# Auunuciator.net
KiCad netlist of a schematic drawn in Altium Designer
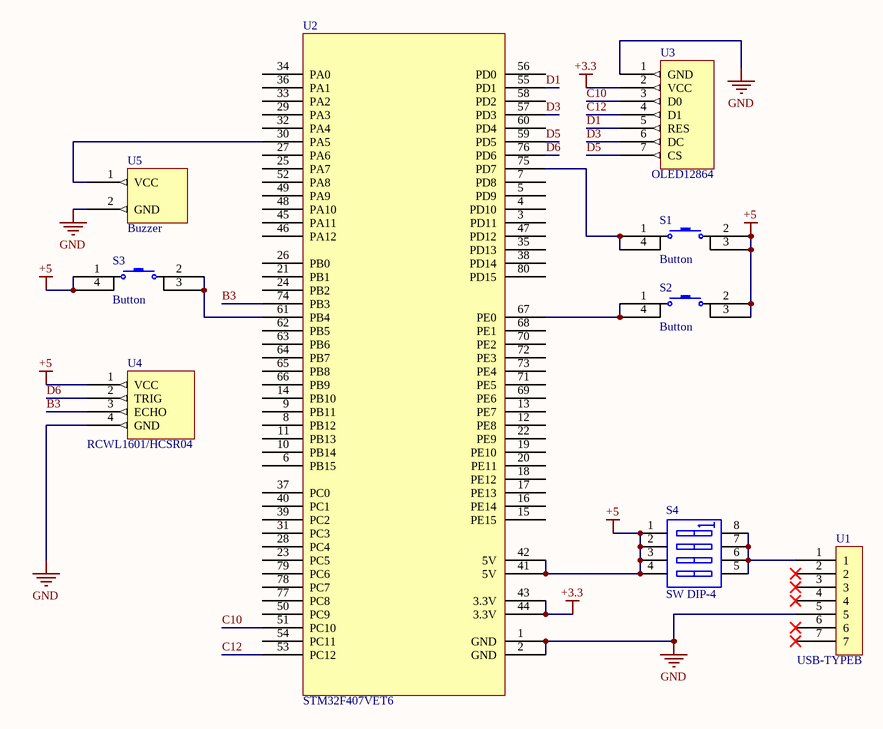
[diagram p0: Auunuciator.SchDoc]

(export (version "E")
  (design (tool "Eeschema 10.0.6"))
  (components
    (comp (ref "S1") (value "Button") (libsource (lib "User SchLib") (part "4PinButton")))
    (comp (ref "S2") (value "Button") (libsource (lib "User SchLib") (part "4PinButton")))
    (comp (ref "S3") (value "Button") (libsource (lib "User SchLib") (part "4PinButton")))
    (comp (ref "S4")
      (value "SW DIP-4")
      (footprint "DIP-8")
      (description "DIP Switch, 4 Position, SPST")
      (fields (field (name "PUBLISHER") "Altium Limited"))
      (libsource (lib "Miscellaneous Devices") (part "SW DIP-4"))
    )
    (comp (ref "U1")
      (value "USB-TYPEB")
      (footprint "microB USB Breakout")
      (libsource (lib "private") (part "HEAD7A"))
    )
    (comp (ref "U2")
      (value "STM32F407VET6")
      (footprint "FK407M1")
      (libsource (lib "核心板元件库") (part "FK407M1"))
    )
    (comp (ref "U3")
      (value "OLED12864")
      (footprint "HDR1X7")
      (description "OLED")
      (libsource (lib "User SchLib") (part "OLED12864"))
    )
    (comp (ref "U4")
      (value "RCWL1601/HCSR04")
      (footprint "HDR1X4")
      (description "Ranging Module")
      (libsource (lib "User SchLib") (part "RCWL1601/HCSR04"))
    )
    (comp (ref "U5")
      (value "Buzzer")
      (footprint "THDZ")
      (description "Active")
      (libsource (lib "User SchLib") (part "Buzzer"))
    )
  )
  (nets
    (net (code "1") (name "+3.3") (class "Default")
      (node (ref "U2") (pin "43") (pinfunction "3.3V_43") (pintype "passive"))
      (node (ref "U2") (pin "44") (pinfunction "3.3V_44") (pintype "passive"))
      (node (ref "U3") (pin "2") (pinfunction "VCC_2") (pintype "output"))
    )
    (net (code "2") (name "+5") (class "Default")
      (node (ref "S1") (pin "2") (pintype "open_collector"))
      (node (ref "S1") (pin "3") (pintype "open_collector"))
      (node (ref "S2") (pin "2") (pintype "open_collector"))
      (node (ref "S2") (pin "3") (pintype "open_collector"))
      (node (ref "S3") (pin "1") (pintype "open_collector"))
      (node (ref "S3") (pin "4") (pintype "open_collector"))
      (node (ref "S4") (pin "1") (pinfunction "A1_1") (pintype "passive"))
      (node (ref "S4") (pin "2") (pinfunction "A2_2") (pintype "passive"))
      (node (ref "S4") (pin "3") (pinfunction "A3_3") (pintype "passive"))
      (node (ref "S4") (pin "4") (pinfunction "A4_4") (pintype "passive"))
      (node (ref "U2") (pin "41") (pinfunction "5V_41") (pintype "passive"))
      (node (ref "U2") (pin "42") (pinfunction "5V_42") (pintype "passive"))
      (node (ref "U4") (pin "1") (pinfunction "VCC_1") (pintype "output"))
    )
    (net (code "3") (name "/B3") (class "Default")
      (node (ref "U2") (pin "74") (pinfunction "PB3_74") (pintype "passive"))
      (node (ref "U4") (pin "3") (pinfunction "ECHO_3") (pintype "output"))
    )
    (net (code "4") (name "/C10") (class "Default")
      (node (ref "U2") (pin "51") (pinfunction "PC10_51") (pintype "passive"))
      (node (ref "U3") (pin "3") (pinfunction "D0_3") (pintype "output"))
    )
    (net (code "5") (name "/C12") (class "Default")
      (node (ref "U2") (pin "53") (pinfunction "PC12_53") (pintype "passive"))
      (node (ref "U3") (pin "4") (pinfunction "D1_4") (pintype "output"))
    )
    (net (code "6") (name "/D1") (class "Default")
      (node (ref "U2") (pin "55") (pinfunction "PD1_55") (pintype "passive"))
      (node (ref "U3") (pin "5") (pinfunction "RES_5") (pintype "output"))
    )
    (net (code "7") (name "/D3") (class "Default")
      (node (ref "U2") (pin "57") (pinfunction "PD3_57") (pintype "passive"))
      (node (ref "U3") (pin "6") (pinfunction "DC_6") (pintype "output"))
    )
    (net (code "8") (name "/D5") (class "Default")
      (node (ref "U2") (pin "59") (pinfunction "PD5_59") (pintype "passive"))
      (node (ref "U3") (pin "7") (pinfunction "CS_7") (pintype "output"))
    )
    (net (code "9") (name "/D6") (class "Default")
      (node (ref "U2") (pin "76") (pinfunction "PD6_76") (pintype "passive"))
      (node (ref "U4") (pin "2") (pinfunction "TRIG_2") (pintype "output"))
    )
    (net (code "10") (name "GND") (class "Default")
      (node (ref "U1") (pin "5") (pinfunction "5_5") (pintype "passive"))
      (node (ref "U2") (pin "1") (pinfunction "GND_1") (pintype "passive"))
      (node (ref "U2") (pin "2") (pinfunction "GND_2") (pintype "passive"))
      (node (ref "U3") (pin "1") (pinfunction "GND_1") (pintype "output"))
      (node (ref "U4") (pin "4") (pinfunction "GND_4") (pintype "output"))
      (node (ref "U5") (pin "2") (pinfunction "GND_2") (pintype "output"))
    )
    (net (code "11") (name "Net-(S4-B1)") (class "Default")
      (node (ref "S4") (pin "5") (pinfunction "B4_5") (pintype "passive"))
      (node (ref "S4") (pin "6") (pinfunction "B3_6") (pintype "passive"))
      (node (ref "S4") (pin "7") (pinfunction "B2_7") (pintype "passive"))
      (node (ref "S4") (pin "8") (pinfunction "B1_8") (pintype "passive"))
      (node (ref "U1") (pin "1") (pinfunction "1_1") (pintype "passive"))
    )
    (net (code "12") (name "Net-(U2-PA5)") (class "Default")
      (node (ref "U2") (pin "30") (pinfunction "PA5_30") (pintype "passive"))
      (node (ref "U5") (pin "1") (pinfunction "VCC_1") (pintype "output"))
    )
    (net (code "13") (name "Net-(U2-PB4)") (class "Default")
      (node (ref "S3") (pin "2") (pintype "open_collector"))
      (node (ref "S3") (pin "3") (pintype "open_collector"))
      (node (ref "U2") (pin "61") (pinfunction "PB4_61") (pintype "passive"))
    )
    (net (code "14") (name "Net-(U2-PD7)") (class "Default")
      (node (ref "S1") (pin "1") (pintype "open_collector"))
      (node (ref "S1") (pin "4") (pintype "open_collector"))
      (node (ref "U2") (pin "75") (pinfunction "PD7_75") (pintype "passive"))
    )
    (net (code "15") (name "Net-(U2-PE0)") (class "Default")
      (node (ref "S2") (pin "1") (pintype "open_collector"))
      (node (ref "S2") (pin "4") (pintype "open_collector"))
      (node (ref "U2") (pin "67") (pinfunction "PE0_67") (pintype "passive"))
    )
    (net (code "16") (name "unconnected-(U1-Pad2)") (class "Default")
      (node (ref "U1") (pin "2") (pinfunction "2_2") (pintype "passive+no_connect"))
    )
    (net (code "17") (name "unconnected-(U1-Pad3)") (class "Default")
      (node (ref "U1") (pin "3") (pinfunction "3_3") (pintype "passive+no_connect"))
    )
    (net (code "18") (name "unconnected-(U1-Pad4)") (class "Default")
      (node (ref "U1") (pin "4") (pinfunction "4_4") (pintype "passive+no_connect"))
    )
    (net (code "19") (name "unconnected-(U1-Pad6)") (class "Default")
      (node (ref "U1") (pin "6") (pinfunction "6_6") (pintype "passive+no_connect"))
    )
    (net (code "20") (name "unconnected-(U1-Pad7)") (class "Default")
      (node (ref "U1") (pin "7") (pinfunction "7_7") (pintype "passive+no_connect"))
    )
    (net (code "21") (name "unconnected-(U2-PA0-Pad34)") (class "Default")
      (node (ref "U2") (pin "34") (pinfunction "PA0_34") (pintype "passive"))
    )
    (net (code "22") (name "unconnected-(U2-PA1-Pad36)") (class "Default")
      (node (ref "U2") (pin "36") (pinfunction "PA1_36") (pintype "passive"))
    )
    (net (code "23") (name "unconnected-(U2-PA2-Pad33)") (class "Default")
      (node (ref "U2") (pin "33") (pinfunction "PA2_33") (pintype "passive"))
    )
    (net (code "24") (name "unconnected-(U2-PA3-Pad29)") (class "Default")
      (node (ref "U2") (pin "29") (pinfunction "PA3_29") (pintype "passive"))
    )
    (net (code "25") (name "unconnected-(U2-PA4-Pad32)") (class "Default")
      (node (ref "U2") (pin "32") (pinfunction "PA4_32") (pintype "passive"))
    )
    (net (code "26") (name "unconnected-(U2-PA6-Pad27)") (class "Default")
      (node (ref "U2") (pin "27") (pinfunction "PA6_27") (pintype "passive"))
    )
    (net (code "27") (name "unconnected-(U2-PA7-Pad25)") (class "Default")
      (node (ref "U2") (pin "25") (pinfunction "PA7_25") (pintype "passive"))
    )
    (net (code "28") (name "unconnected-(U2-PA8-Pad52)") (class "Default")
      (node (ref "U2") (pin "52") (pinfunction "PA8_52") (pintype "passive"))
    )
    (net (code "29") (name "unconnected-(U2-PA9-Pad49)") (class "Default")
      (node (ref "U2") (pin "49") (pinfunction "PA9_49") (pintype "passive"))
    )
    (net (code "30") (name "unconnected-(U2-PA10-Pad48)") (class "Default")
      (node (ref "U2") (pin "48") (pinfunction "PA10_48") (pintype "passive"))
    )
    (net (code "31") (name "unconnected-(U2-PA11-Pad45)") (class "Default")
      (node (ref "U2") (pin "45") (pinfunction "PA11_45") (pintype "passive"))
    )
    (net (code "32") (name "unconnected-(U2-PA12-Pad46)") (class "Default")
      (node (ref "U2") (pin "46") (pinfunction "PA12_46") (pintype "passive"))
    )
    (net (code "33") (name "unconnected-(U2-PB0-Pad26)") (class "Default")
      (node (ref "U2") (pin "26") (pinfunction "PB0_26") (pintype "passive"))
    )
    (net (code "34") (name "unconnected-(U2-PB1-Pad21)") (class "Default")
      (node (ref "U2") (pin "21") (pinfunction "PB1_21") (pintype "passive"))
    )
    (net (code "35") (name "unconnected-(U2-PB2-Pad24)") (class "Default")
      (node (ref "U2") (pin "24") (pinfunction "PB2_24") (pintype "passive"))
    )
    (net (code "36") (name "unconnected-(U2-PB5-Pad62)") (class "Default")
      (node (ref "U2") (pin "62") (pinfunction "PB5_62") (pintype "passive"))
    )
    (net (code "37") (name "unconnected-(U2-PB6-Pad63)") (class "Default")
      (node (ref "U2") (pin "63") (pinfunction "PB6_63") (pintype "passive"))
    )
    (net (code "38") (name "unconnected-(U2-PB7-Pad64)") (class "Default")
      (node (ref "U2") (pin "64") (pinfunction "PB7_64") (pintype "passive"))
    )
    (net (code "39") (name "unconnected-(U2-PB8-Pad65)") (class "Default")
      (node (ref "U2") (pin "65") (pinfunction "PB8_65") (pintype "passive"))
    )
    (net (code "40") (name "unconnected-(U2-PB9-Pad66)") (class "Default")
      (node (ref "U2") (pin "66") (pinfunction "PB9_66") (pintype "passive"))
    )
    (net (code "41") (name "unconnected-(U2-PB10-Pad14)") (class "Default")
      (node (ref "U2") (pin "14") (pinfunction "PB10_14") (pintype "passive"))
    )
    (net (code "42") (name "unconnected-(U2-PB11-Pad9)") (class "Default")
      (node (ref "U2") (pin "9") (pinfunction "PB11_9") (pintype "passive"))
    )
    (net (code "43") (name "unconnected-(U2-PB12-Pad8)") (class "Default")
      (node (ref "U2") (pin "8") (pinfunction "PB12_8") (pintype "passive"))
    )
    (net (code "44") (name "unconnected-(U2-PB13-Pad11)") (class "Default")
      (node (ref "U2") (pin "11") (pinfunction "PB13_11") (pintype "passive"))
    )
    (net (code "45") (name "unconnected-(U2-PB14-Pad10)") (class "Default")
      (node (ref "U2") (pin "10") (pinfunction "PB14_10") (pintype "passive"))
    )
    (net (code "46") (name "unconnected-(U2-PB15-Pad6)") (class "Default")
      (node (ref "U2") (pin "6") (pinfunction "PB15_6") (pintype "passive"))
    )
    (net (code "47") (name "unconnected-(U2-PC0-Pad37)") (class "Default")
      (node (ref "U2") (pin "37") (pinfunction "PC0_37") (pintype "passive"))
    )
    (net (code "48") (name "unconnected-(U2-PC1-Pad40)") (class "Default")
      (node (ref "U2") (pin "40") (pinfunction "PC1_40") (pintype "passive"))
    )
    (net (code "49") (name "unconnected-(U2-PC2-Pad39)") (class "Default")
      (node (ref "U2") (pin "39") (pinfunction "PC2_39") (pintype "passive"))
    )
    (net (code "50") (name "unconnected-(U2-PC3-Pad31)") (class "Default")
      (node (ref "U2") (pin "31") (pinfunction "PC3_31") (pintype "passive"))
    )
    (net (code "51") (name "unconnected-(U2-PC4-Pad28)") (class "Default")
      (node (ref "U2") (pin "28") (pinfunction "PC4_28") (pintype "passive"))
    )
    (net (code "52") (name "unconnected-(U2-PC5-Pad23)") (class "Default")
      (node (ref "U2") (pin "23") (pinfunction "PC5_23") (pintype "passive"))
    )
    (net (code "53") (name "unconnected-(U2-PC6-Pad79)") (class "Default")
      (node (ref "U2") (pin "79") (pinfunction "PC6_79") (pintype "passive"))
    )
    (net (code "54") (name "unconnected-(U2-PC7-Pad78)") (class "Default")
      (node (ref "U2") (pin "78") (pinfunction "PC7_78") (pintype "passive"))
    )
    (net (code "55") (name "unconnected-(U2-PC8-Pad77)") (class "Default")
      (node (ref "U2") (pin "77") (pinfunction "PC8_77") (pintype "passive"))
    )
    (net (code "56") (name "unconnected-(U2-PC9-Pad50)") (class "Default")
      (node (ref "U2") (pin "50") (pinfunction "PC9_50") (pintype "passive"))
    )
    (net (code "57") (name "unconnected-(U2-PC11-Pad54)") (class "Default")
      (node (ref "U2") (pin "54") (pinfunction "PC11_54") (pintype "passive"))
    )
    (net (code "58") (name "unconnected-(U2-PD0-Pad56)") (class "Default")
      (node (ref "U2") (pin "56") (pinfunction "PD0_56") (pintype "passive"))
    )
    (net (code "59") (name "unconnected-(U2-PD2-Pad58)") (class "Default")
      (node (ref "U2") (pin "58") (pinfunction "PD2_58") (pintype "passive"))
    )
    (net (code "60") (name "unconnected-(U2-PD4-Pad60)") (class "Default")
      (node (ref "U2") (pin "60") (pinfunction "PD4_60") (pintype "passive"))
    )
    (net (code "61") (name "unconnected-(U2-PD8-Pad7)") (class "Default")
      (node (ref "U2") (pin "7") (pinfunction "PD8_7") (pintype "passive"))
    )
    (net (code "62") (name "unconnected-(U2-PD9-Pad5)") (class "Default")
      (node (ref "U2") (pin "5") (pinfunction "PD9_5") (pintype "passive"))
    )
    (net (code "63") (name "unconnected-(U2-PD10-Pad4)") (class "Default")
      (node (ref "U2") (pin "4") (pinfunction "PD10_4") (pintype "passive"))
    )
    (net (code "64") (name "unconnected-(U2-PD11-Pad3)") (class "Default")
      (node (ref "U2") (pin "3") (pinfunction "PD11_3") (pintype "passive"))
    )
    (net (code "65") (name "unconnected-(U2-PD12-Pad47)") (class "Default")
      (node (ref "U2") (pin "47") (pinfunction "PD12_47") (pintype "passive"))
    )
    (net (code "66") (name "unconnected-(U2-PD13-Pad35)") (class "Default")
      (node (ref "U2") (pin "35") (pinfunction "PD13_35") (pintype "passive"))
    )
    (net (code "67") (name "unconnected-(U2-PD14-Pad38)") (class "Default")
      (node (ref "U2") (pin "38") (pinfunction "PD14_38") (pintype "passive"))
    )
    (net (code "68") (name "unconnected-(U2-PD15-Pad80)") (class "Default")
      (node (ref "U2") (pin "80") (pinfunction "PD15_80") (pintype "passive"))
    )
    (net (code "69") (name "unconnected-(U2-PE1-Pad68)") (class "Default")
      (node (ref "U2") (pin "68") (pinfunction "PE1_68") (pintype "passive"))
    )
    (net (code "70") (name "unconnected-(U2-PE2-Pad70)") (class "Default")
      (node (ref "U2") (pin "70") (pinfunction "PE2_70") (pintype "passive"))
    )
    (net (code "71") (name "unconnected-(U2-PE3-Pad72)") (class "Default")
      (node (ref "U2") (pin "72") (pinfunction "PE3_72") (pintype "passive"))
    )
    (net (code "72") (name "unconnected-(U2-PE4-Pad73)") (class "Default")
      (node (ref "U2") (pin "73") (pinfunction "PE4_73") (pintype "passive"))
    )
    (net (code "73") (name "unconnected-(U2-PE5-Pad71)") (class "Default")
      (node (ref "U2") (pin "71") (pinfunction "PE5_71") (pintype "passive"))
    )
    (net (code "74") (name "unconnected-(U2-PE6-Pad69)") (class "Default")
      (node (ref "U2") (pin "69") (pinfunction "PE6_69") (pintype "passive"))
    )
    (net (code "75") (name "unconnected-(U2-PE7-Pad13)") (class "Default")
      (node (ref "U2") (pin "13") (pinfunction "PE7_13") (pintype "passive"))
    )
    (net (code "76") (name "unconnected-(U2-PE8-Pad12)") (class "Default")
      (node (ref "U2") (pin "12") (pinfunction "PE8_12") (pintype "passive"))
    )
    (net (code "77") (name "unconnected-(U2-PE9-Pad22)") (class "Default")
      (node (ref "U2") (pin "22") (pinfunction "PE9_22") (pintype "passive"))
    )
    (net (code "78") (name "unconnected-(U2-PE10-Pad19)") (class "Default")
      (node (ref "U2") (pin "19") (pinfunction "PE10_19") (pintype "passive"))
    )
    (net (code "79") (name "unconnected-(U2-PE11-Pad20)") (class "Default")
      (node (ref "U2") (pin "20") (pinfunction "PE11_20") (pintype "passive"))
    )
    (net (code "80") (name "unconnected-(U2-PE12-Pad18)") (class "Default")
      (node (ref "U2") (pin "18") (pinfunction "PE12_18") (pintype "passive"))
    )
    (net (code "81") (name "unconnected-(U2-PE13-Pad17)") (class "Default")
      (node (ref "U2") (pin "17") (pinfunction "PE13_17") (pintype "passive"))
    )
    (net (code "82") (name "unconnected-(U2-PE14-Pad16)") (class "Default")
      (node (ref "U2") (pin "16") (pinfunction "PE14_16") (pintype "passive"))
    )
    (net (code "83") (name "unconnected-(U2-PE15-Pad15)") (class "Default")
      (node (ref "U2") (pin "15") (pinfunction "PE15_15") (pintype "passive"))
    )
  )
)
